# cc2650_rev2.net
KiCad netlist of a schematic drawn in EAGLE
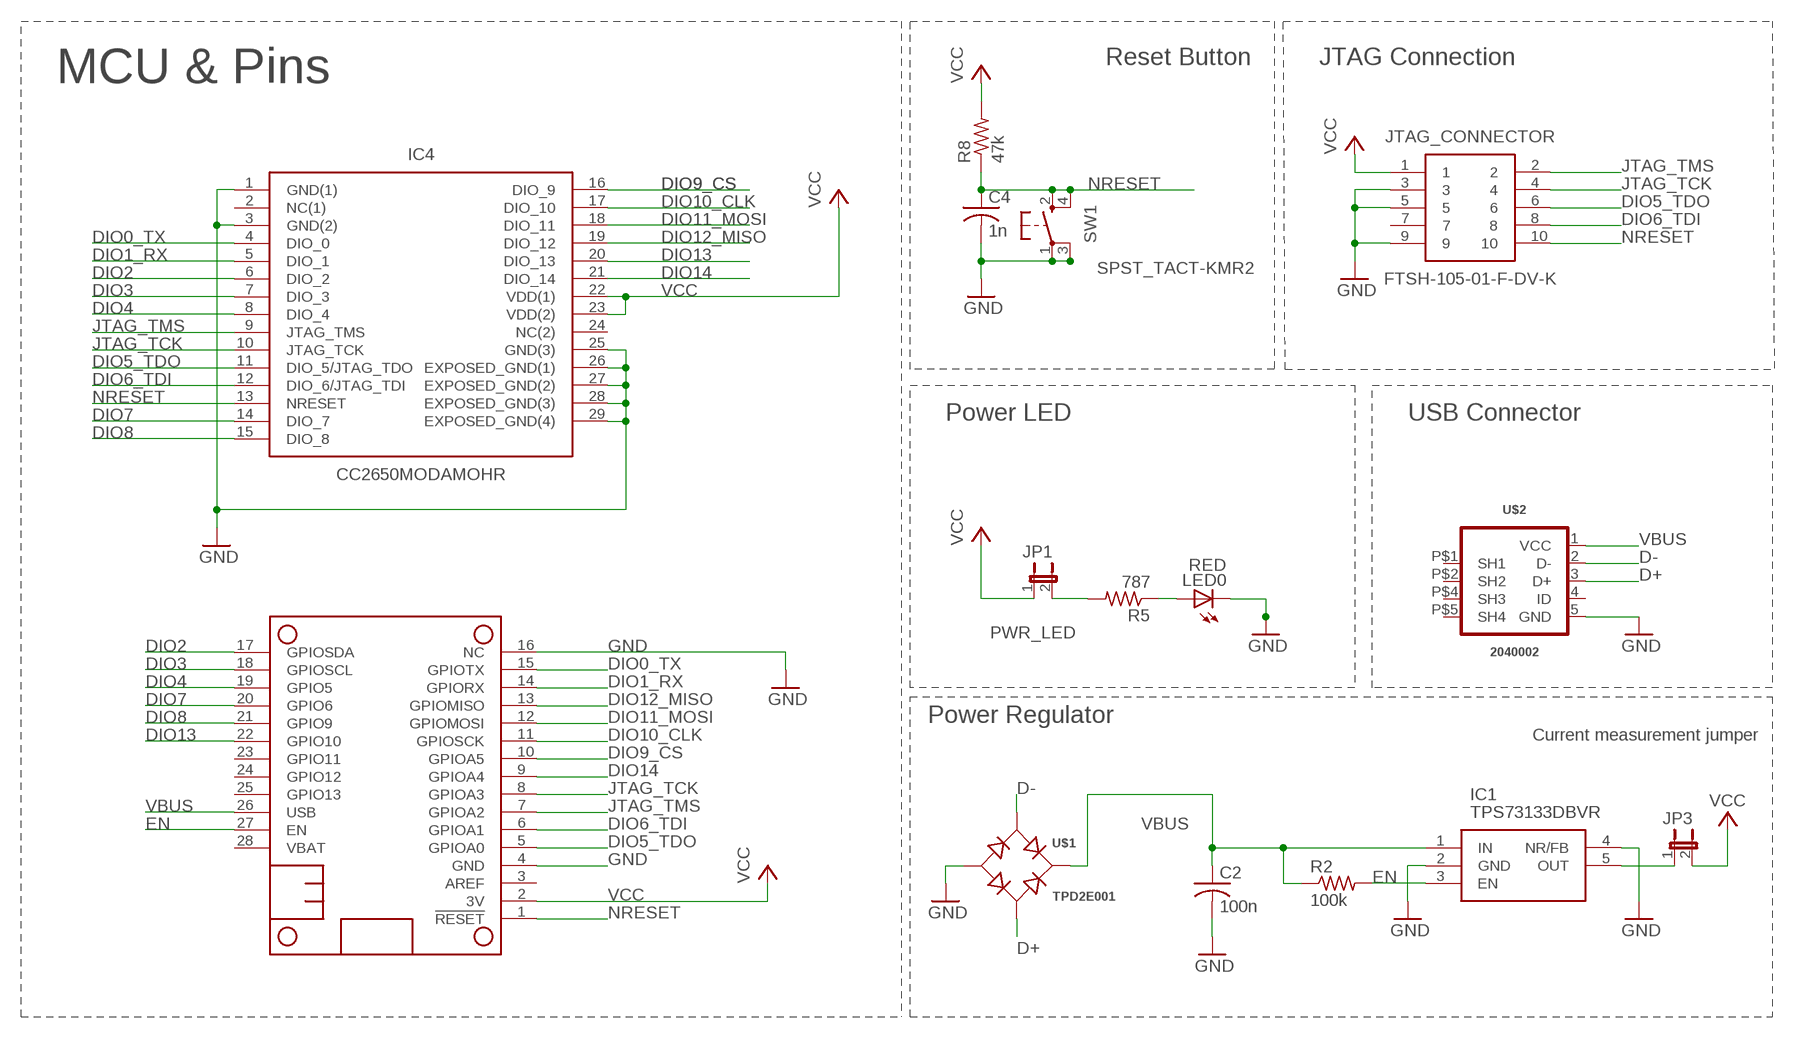
[diagram p0: schematic, sheet 1]
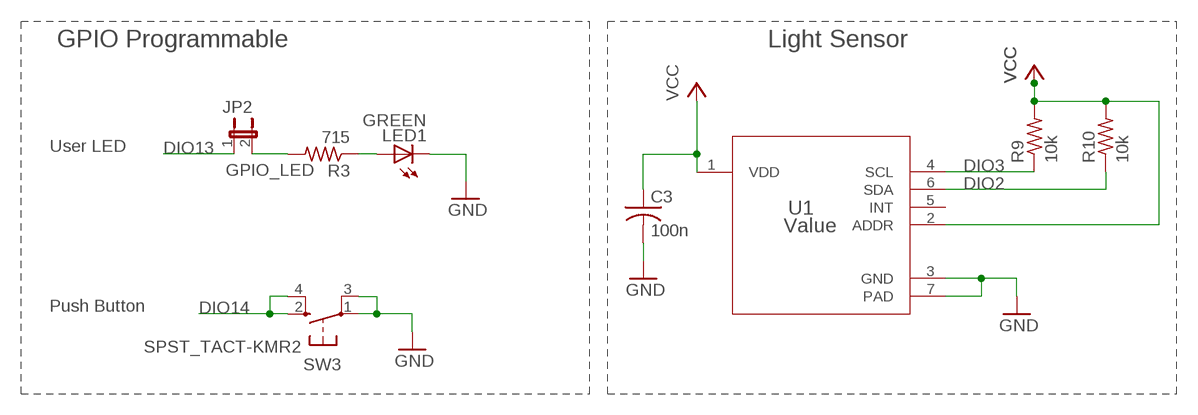
[diagram p1: schematic, sheet 2]

(export (version "E")
  (design (tool "Eeschema 10.0.6"))
  (components
    (comp (ref "C3")
      (value "100n")
      (footprint "eagle-import:C1206")
      (libsource (lib "eagle-import") (part "C-USC1206"))
    )
    (comp (ref "JP2")
      (value "GPIO_LED")
      (footprint "eagle-import:JP1M")
      (fields (field (name "MPN") "2211S-02G"))
      (libsource (lib "eagle-import") (part "JP1M"))
    )
    (comp (ref "LED1")
      (value "GREEN")
      (footprint "eagle-import:CHIPLED_0603")
      (libsource (lib "eagle-import") (part "LEDCHIPLED_0603"))
    )
    (comp (ref "R3")
      (value "715")
      (footprint "eagle-import:R0603")
      (fields (field (name "MPN") "RC0603JR-07100KL"))
      (libsource (lib "eagle-import") (part "R-US_R0603"))
    )
    (comp (ref "R9")
      (value "10k")
      (footprint "eagle-import:R1206")
      (libsource (lib "eagle-import") (part "R-US_R1206"))
    )
    (comp (ref "R10")
      (value "10k")
      (footprint "eagle-import:R1206")
      (libsource (lib "eagle-import") (part "R-US_R1206"))
    )
    (comp (ref "SW3")
      (value "SPST_TACT-KMR2")
      (footprint "eagle-import:KMR2")
      (fields (field (name "MPN") "KMR241G LFS"))
      (libsource (lib "eagle-import") (part "SPST_TACT-KMR2"))
    )
    (comp (ref "U1")
      (value "Value")
      (footprint "eagle-import:DNP0006A")
      (fields (field (name "MANUFACTURER") "Texas Instruments") (field (name "PARTNUMBER") "OPT3001DNP"))
      (libsource (lib "eagle-import") (part "OPT3001DNPR"))
    )
    (comp (ref "C2")
      (value "100n")
      (footprint "eagle-import:C1206")
      (libsource (lib "eagle-import") (part "C-USC1206"))
    )
    (comp (ref "C4")
      (value "1n")
      (footprint "eagle-import:C1206")
      (libsource (lib "eagle-import") (part "C-USC1206"))
    )
    (comp (ref "IC1")
      (value "TPS73133DBVR")
      (footprint "eagle-import:SOT95P280X145-5N")
      (fields (field (name "RS_PART_NUMBER") "6613970"))
      (libsource (lib "eagle-import") (part "TPS73133DBVR"))
    )
    (comp (ref "IC4")
      (value "CC2650MODAMOHR")
      (footprint "eagle-import:MOH0029A")
      (libsource (lib "eagle-import") (part "CC2650MODAMOHR"))
    )
    (comp (ref "JP1")
      (value "PWR_LED")
      (footprint "eagle-import:JP1M")
      (fields (field (name "MPN") "2211S-02G"))
      (libsource (lib "eagle-import") (part "JP1M"))
    )
    (comp (ref "JP3")
      (value "PWR_LED")
      (footprint "eagle-import:JP1M")
      (fields (field (name "MPN") "2211S-02G"))
      (libsource (lib "eagle-import") (part "JP1M"))
    )
    (comp (ref "JTAG_CONNECTOR")
      (value "FTSH-105-01-F-DV-K")
      (footprint "eagle-import:SAMTEC_FTSH-105-01-L-DV")
      (libsource (lib "eagle-import") (part "FTSH-105-01-F-DV-K"))
    )
    (comp (ref "LED0")
      (value "RED")
      (footprint "eagle-import:CHIPLED_0603")
      (libsource (lib "eagle-import") (part "LEDCHIPLED_0603"))
    )
    (comp (ref "MS1")
      (value "FEATHERWING_NODIM")
      (footprint "eagle-import:FEATHERWING_DIM")
      (libsource (lib "eagle-import") (part "FEATHERWING_NODIM"))
    )
    (comp (ref "R2")
      (value "100k")
      (footprint "eagle-import:R1206")
      (libsource (lib "eagle-import") (part "R-US_R1206"))
    )
    (comp (ref "R5")
      (value "787")
      (footprint "eagle-import:R0603")
      (fields (field (name "MPN") "RC0603JR-07100KL"))
      (libsource (lib "eagle-import") (part "R-US_R0603"))
    )
    (comp (ref "R8")
      (value "47k")
      (footprint "eagle-import:R1206")
      (libsource (lib "eagle-import") (part "R-US_R1206"))
    )
    (comp (ref "SW1")
      (value "SPST_TACT-KMR2")
      (footprint "eagle-import:KMR2")
      (fields (field (name "MPN") "KMR241G LFS"))
      (libsource (lib "eagle-import") (part "SPST_TACT-KMR2"))
    )
    (comp (ref "U$1")
      (value "TPD2E001")
      (footprint "eagle-import:SOT-143")
      (libsource (lib "eagle-import") (part "TPD2E001"))
    )
    (comp (ref "U$2")
      (value "2040002")
      (footprint "eagle-import:2040002")
      (libsource (lib "eagle-import") (part "2040002"))
    )
  )
  (nets
    (net (code "1") (name "D+") (class "Default")
      (node (ref "U$1") (pin "3") (pinfunction "AC2_3") (pintype "passive"))
      (node (ref "U$2") (pin "3") (pinfunction "D+_3") (pintype "bidirectional"))
    )
    (net (code "2") (name "D-") (class "Default")
      (node (ref "U$1") (pin "2") (pinfunction "AC1_2") (pintype "passive"))
      (node (ref "U$2") (pin "2") (pinfunction "D-_2") (pintype "bidirectional"))
    )
    (net (code "3") (name "DIO0_TX") (class "Default")
      (node (ref "IC4") (pin "4") (pinfunction "DIO_0_4") (pintype "passive"))
      (node (ref "MS1") (pin "15") (pinfunction "GPIOTX_15") (pintype "bidirectional"))
    )
    (net (code "4") (name "DIO1_RX") (class "Default")
      (node (ref "IC4") (pin "5") (pinfunction "DIO_1_5") (pintype "passive"))
      (node (ref "MS1") (pin "14") (pinfunction "GPIORX_14") (pintype "bidirectional"))
    )
    (net (code "5") (name "DIO2") (class "Default")
      (node (ref "IC4") (pin "6") (pinfunction "DIO_2_6") (pintype "passive"))
      (node (ref "MS1") (pin "17") (pinfunction "GPIOSDA_17") (pintype "bidirectional"))
      (node (ref "R10") (pin "1") (pinfunction "1_1") (pintype "passive"))
      (node (ref "U1") (pin "6") (pinfunction "SDA_6") (pintype "input"))
    )
    (net (code "6") (name "DIO3") (class "Default")
      (node (ref "IC4") (pin "7") (pinfunction "DIO_3_7") (pintype "passive"))
      (node (ref "MS1") (pin "18") (pinfunction "GPIOSCL_18") (pintype "bidirectional"))
      (node (ref "R9") (pin "1") (pinfunction "1_1") (pintype "passive"))
      (node (ref "U1") (pin "4") (pinfunction "SCL_4") (pintype "input"))
    )
    (net (code "7") (name "DIO4") (class "Default")
      (node (ref "IC4") (pin "8") (pinfunction "DIO_4_8") (pintype "passive"))
      (node (ref "MS1") (pin "19") (pinfunction "GPIO5_19") (pintype "bidirectional"))
    )
    (net (code "8") (name "DIO5_TDO") (class "Default")
      (node (ref "IC4") (pin "11") (pinfunction "DIO_5/JTAG_TDO_11") (pintype "passive"))
      (node (ref "JTAG_CONNECTOR") (pin "6") (pinfunction "6_6") (pintype "passive"))
      (node (ref "MS1") (pin "5") (pinfunction "GPIOA0_5") (pintype "bidirectional"))
    )
    (net (code "9") (name "DIO6_TDI") (class "Default")
      (node (ref "IC4") (pin "12") (pinfunction "DIO_6/JTAG_TDI_12") (pintype "passive"))
      (node (ref "JTAG_CONNECTOR") (pin "8") (pinfunction "8_8") (pintype "passive"))
      (node (ref "MS1") (pin "6") (pinfunction "GPIOA1_6") (pintype "bidirectional"))
    )
    (net (code "10") (name "DIO7") (class "Default")
      (node (ref "IC4") (pin "14") (pinfunction "DIO_7_14") (pintype "passive"))
      (node (ref "MS1") (pin "20") (pinfunction "GPIO6_20") (pintype "bidirectional"))
    )
    (net (code "11") (name "DIO8") (class "Default")
      (node (ref "IC4") (pin "15") (pinfunction "DIO_8_15") (pintype "passive"))
      (node (ref "MS1") (pin "21") (pinfunction "GPIO9_21") (pintype "bidirectional"))
    )
    (net (code "12") (name "DIO9_CS") (class "Default")
      (node (ref "IC4") (pin "16") (pinfunction "DIO_9_16") (pintype "passive"))
      (node (ref "MS1") (pin "10") (pinfunction "GPIOA5_10") (pintype "bidirectional"))
    )
    (net (code "13") (name "DIO10_CLK") (class "Default")
      (node (ref "IC4") (pin "17") (pinfunction "DIO_10_17") (pintype "passive"))
      (node (ref "MS1") (pin "11") (pinfunction "GPIOSCK_11") (pintype "bidirectional"))
    )
    (net (code "14") (name "DIO11_MOSI") (class "Default")
      (node (ref "IC4") (pin "18") (pinfunction "DIO_11_18") (pintype "passive"))
      (node (ref "MS1") (pin "12") (pinfunction "GPIOMOSI_12") (pintype "bidirectional"))
    )
    (net (code "15") (name "DIO12_MISO") (class "Default")
      (node (ref "IC4") (pin "19") (pinfunction "DIO_12_19") (pintype "passive"))
      (node (ref "MS1") (pin "13") (pinfunction "GPIOMISO_13") (pintype "bidirectional"))
    )
    (net (code "16") (name "DIO13") (class "Default")
      (node (ref "IC4") (pin "20") (pinfunction "DIO_13_20") (pintype "passive"))
      (node (ref "JP2") (pin "1") (pinfunction "1_1") (pintype "passive"))
      (node (ref "MS1") (pin "22") (pinfunction "GPIO10_22") (pintype "bidirectional"))
    )
    (net (code "17") (name "DIO14") (class "Default")
      (node (ref "IC4") (pin "21") (pinfunction "DIO_14_21") (pintype "passive"))
      (node (ref "MS1") (pin "9") (pinfunction "GPIOA4_9") (pintype "bidirectional"))
      (node (ref "SW3") (pin "2") (pinfunction "S_2") (pintype "passive"))
      (node (ref "SW3") (pin "4") (pinfunction "S1_4") (pintype "passive"))
    )
    (net (code "18") (name "EN") (class "Default")
      (node (ref "IC1") (pin "3") (pinfunction "EN_3") (pintype "input"))
      (node (ref "MS1") (pin "27") (pinfunction "EN_27") (pintype "passive"))
      (node (ref "R2") (pin "2") (pinfunction "2_2") (pintype "passive"))
    )
    (net (code "19") (name "GND") (class "Default")
      (node (ref "C2") (pin "2") (pinfunction "2_2") (pintype "passive"))
      (node (ref "C3") (pin "2") (pinfunction "2_2") (pintype "passive"))
      (node (ref "C4") (pin "2") (pinfunction "2_2") (pintype "passive"))
      (node (ref "IC1") (pin "2") (pinfunction "GND_2") (pintype "input"))
      (node (ref "IC1") (pin "4") (pinfunction "NR/FB_4") (pintype "input"))
      (node (ref "IC4") (pin "1") (pinfunction "GND(1)_1") (pintype "passive"))
      (node (ref "IC4") (pin "25") (pinfunction "GND(3)_25") (pintype "passive"))
      (node (ref "IC4") (pin "26") (pinfunction "EXPOSED_GND(1)_26") (pintype "passive"))
      (node (ref "IC4") (pin "27") (pinfunction "EXPOSED_GND(2)_27") (pintype "passive"))
      (node (ref "IC4") (pin "28") (pinfunction "EXPOSED_GND(3)_28") (pintype "passive"))
      (node (ref "IC4") (pin "29") (pinfunction "EXPOSED_GND(4)_29") (pintype "passive"))
      (node (ref "IC4") (pin "3") (pinfunction "GND(2)_3") (pintype "passive"))
      (node (ref "JTAG_CONNECTOR") (pin "3") (pinfunction "3_3") (pintype "passive"))
      (node (ref "JTAG_CONNECTOR") (pin "5") (pinfunction "5_5") (pintype "passive"))
      (node (ref "JTAG_CONNECTOR") (pin "9") (pinfunction "9_9") (pintype "passive"))
      (node (ref "LED0") (pin "C") (pinfunction "C_C") (pintype "passive"))
      (node (ref "LED1") (pin "C") (pinfunction "C_C") (pintype "passive"))
      (node (ref "MS1") (pin "16") (pinfunction "NC_16") (pintype "passive"))
      (node (ref "MS1") (pin "4") (pinfunction "GND_4") (pintype "power_in"))
      (node (ref "SW1") (pin "1") (pinfunction "P_1") (pintype "passive"))
      (node (ref "SW1") (pin "3") (pinfunction "P1_3") (pintype "passive"))
      (node (ref "SW3") (pin "1") (pinfunction "P_1") (pintype "passive"))
      (node (ref "SW3") (pin "3") (pinfunction "P1_3") (pintype "passive"))
      (node (ref "U$1") (pin "1") (pinfunction "-_1") (pintype "passive"))
      (node (ref "U$2") (pin "5") (pinfunction "GND_5") (pintype "bidirectional"))
      (node (ref "U1") (pin "3") (pinfunction "GND_3") (pintype "power_in"))
      (node (ref "U1") (pin "7") (pinfunction "PAD_7") (pintype "passive"))
    )
    (net (code "20") (name "JTAG_TCK") (class "Default")
      (node (ref "IC4") (pin "10") (pinfunction "JTAG_TCK_10") (pintype "passive"))
      (node (ref "JTAG_CONNECTOR") (pin "4") (pinfunction "4_4") (pintype "passive"))
      (node (ref "MS1") (pin "8") (pinfunction "GPIOA3_8") (pintype "bidirectional"))
    )
    (net (code "21") (name "JTAG_TMS") (class "Default")
      (node (ref "IC4") (pin "9") (pinfunction "JTAG_TMS_9") (pintype "passive"))
      (node (ref "JTAG_CONNECTOR") (pin "2") (pinfunction "2_2") (pintype "passive"))
      (node (ref "MS1") (pin "7") (pinfunction "GPIOA2_7") (pintype "bidirectional"))
    )
    (net (code "22") (name "NRESET") (class "Default")
      (node (ref "C4") (pin "1") (pinfunction "1_1") (pintype "passive"))
      (node (ref "IC4") (pin "13") (pinfunction "NRESET_13") (pintype "passive"))
      (node (ref "JTAG_CONNECTOR") (pin "10") (pinfunction "10_10") (pintype "passive"))
      (node (ref "MS1") (pin "1") (pinfunction "~{RESET}_1") (pintype "input"))
      (node (ref "R8") (pin "1") (pinfunction "1_1") (pintype "passive"))
      (node (ref "SW1") (pin "2") (pinfunction "S_2") (pintype "passive"))
      (node (ref "SW1") (pin "4") (pinfunction "S1_4") (pintype "passive"))
    )
    (net (code "23") (name "Net-(IC1-OUT)") (class "Default")
      (node (ref "IC1") (pin "5") (pinfunction "OUT_5") (pintype "input"))
      (node (ref "JP3") (pin "1") (pinfunction "1_1") (pintype "passive"))
    )
    (net (code "24") (name "Net-(JP1-Pad2)") (class "Default")
      (node (ref "JP1") (pin "2") (pinfunction "2_2") (pintype "passive"))
      (node (ref "R5") (pin "2") (pinfunction "2_2") (pintype "passive"))
    )
    (net (code "25") (name "Net-(JP2-Pad2)") (class "Default")
      (node (ref "JP2") (pin "2") (pinfunction "2_2") (pintype "passive"))
      (node (ref "R3") (pin "2") (pinfunction "2_2") (pintype "passive"))
    )
    (net (code "26") (name "Net-(LED0-PadA)") (class "Default")
      (node (ref "LED0") (pin "A") (pinfunction "A_A") (pintype "passive"))
      (node (ref "R5") (pin "1") (pinfunction "1_1") (pintype "passive"))
    )
    (net (code "27") (name "Net-(LED1-PadA)") (class "Default")
      (node (ref "LED1") (pin "A") (pinfunction "A_A") (pintype "passive"))
      (node (ref "R3") (pin "1") (pinfunction "1_1") (pintype "passive"))
    )
    (net (code "28") (name "VBAT") (class "Default")
      (node (ref "MS1") (pin "28") (pinfunction "VBAT_28") (pintype "power_in"))
    )
    (net (code "29") (name "VBUS") (class "Default")
      (node (ref "C2") (pin "1") (pinfunction "1_1") (pintype "passive"))
      (node (ref "IC1") (pin "1") (pinfunction "IN_1") (pintype "input"))
      (node (ref "MS1") (pin "26") (pinfunction "USB_26") (pintype "power_in"))
      (node (ref "R2") (pin "1") (pinfunction "1_1") (pintype "passive"))
      (node (ref "U$1") (pin "4") (pinfunction "+_4") (pintype "passive"))
      (node (ref "U$2") (pin "1") (pinfunction "VCC_1") (pintype "bidirectional"))
    )
    (net (code "30") (name "VCC") (class "Default")
      (node (ref "C3") (pin "1") (pinfunction "1_1") (pintype "passive"))
      (node (ref "IC4") (pin "22") (pinfunction "VDD(1)_22") (pintype "passive"))
      (node (ref "IC4") (pin "23") (pinfunction "VDD(2)_23") (pintype "passive"))
      (node (ref "JP1") (pin "1") (pinfunction "1_1") (pintype "passive"))
      (node (ref "JP3") (pin "2") (pinfunction "2_2") (pintype "passive"))
      (node (ref "JTAG_CONNECTOR") (pin "1") (pinfunction "1_1") (pintype "passive"))
      (node (ref "MS1") (pin "2") (pinfunction "3V_2") (pintype "power_in"))
      (node (ref "R10") (pin "2") (pinfunction "2_2") (pintype "passive"))
      (node (ref "R8") (pin "2") (pinfunction "2_2") (pintype "passive"))
      (node (ref "R9") (pin "2") (pinfunction "2_2") (pintype "passive"))
      (node (ref "U1") (pin "1") (pinfunction "VDD_1") (pintype "power_in"))
      (node (ref "U1") (pin "2") (pinfunction "ADDR_2") (pintype "input"))
    )
    (net (code "31") (name "unconnected-(IC4-NC(1)-Pad2)") (class "Default")
      (node (ref "IC4") (pin "2") (pinfunction "NC(1)_2") (pintype "passive"))
    )
    (net (code "32") (name "unconnected-(IC4-NC(2)-Pad24)") (class "Default")
      (node (ref "IC4") (pin "24") (pinfunction "NC(2)_24") (pintype "passive"))
    )
    (net (code "33") (name "unconnected-(JTAG_CONNECTOR-Pad7)") (class "Default")
      (node (ref "JTAG_CONNECTOR") (pin "7") (pinfunction "7_7") (pintype "passive"))
    )
    (net (code "34") (name "unconnected-(MS1-AREF-Pad3)") (class "Default")
      (node (ref "MS1") (pin "3") (pinfunction "AREF_3") (pintype "passive"))
    )
    (net (code "35") (name "unconnected-(MS1-GPIO11-Pad23)") (class "Default")
      (node (ref "MS1") (pin "23") (pinfunction "GPIO11_23") (pintype "bidirectional"))
    )
    (net (code "36") (name "unconnected-(MS1-GPIO12-Pad24)") (class "Default")
      (node (ref "MS1") (pin "24") (pinfunction "GPIO12_24") (pintype "bidirectional"))
    )
    (net (code "37") (name "unconnected-(MS1-GPIO13-Pad25)") (class "Default")
      (node (ref "MS1") (pin "25") (pinfunction "GPIO13_25") (pintype "bidirectional"))
    )
    (net (code "38") (name "unconnected-(U$2-ID-Pad4)") (class "Default")
      (node (ref "U$2") (pin "4") (pinfunction "ID_4") (pintype "bidirectional"))
    )
    (net (code "39") (name "unconnected-(U$2-SH1-PadP$1)") (class "Default")
      (node (ref "U$2") (pin "P$1") (pinfunction "SH1_P$1") (pintype "no_connect"))
    )
    (net (code "40") (name "unconnected-(U$2-SH2-PadP$2)") (class "Default")
      (node (ref "U$2") (pin "P$2") (pinfunction "SH2_P$2") (pintype "no_connect"))
    )
    (net (code "41") (name "unconnected-(U$2-SH3-PadP$4)") (class "Default")
      (node (ref "U$2") (pin "P$4") (pinfunction "SH3_P$4") (pintype "no_connect"))
    )
    (net (code "42") (name "unconnected-(U$2-SH4-PadP$5)") (class "Default")
      (node (ref "U$2") (pin "P$5") (pinfunction "SH4_P$5") (pintype "no_connect"))
    )
    (net (code "43") (name "unconnected-(U1-INT-Pad5)") (class "Default")
      (node (ref "U1") (pin "5") (pinfunction "INT_5") (pintype "output"))
    )
  )
)
